# Modbus_RTU.net
KiCad netlist of a schematic drawn in Altium Designer
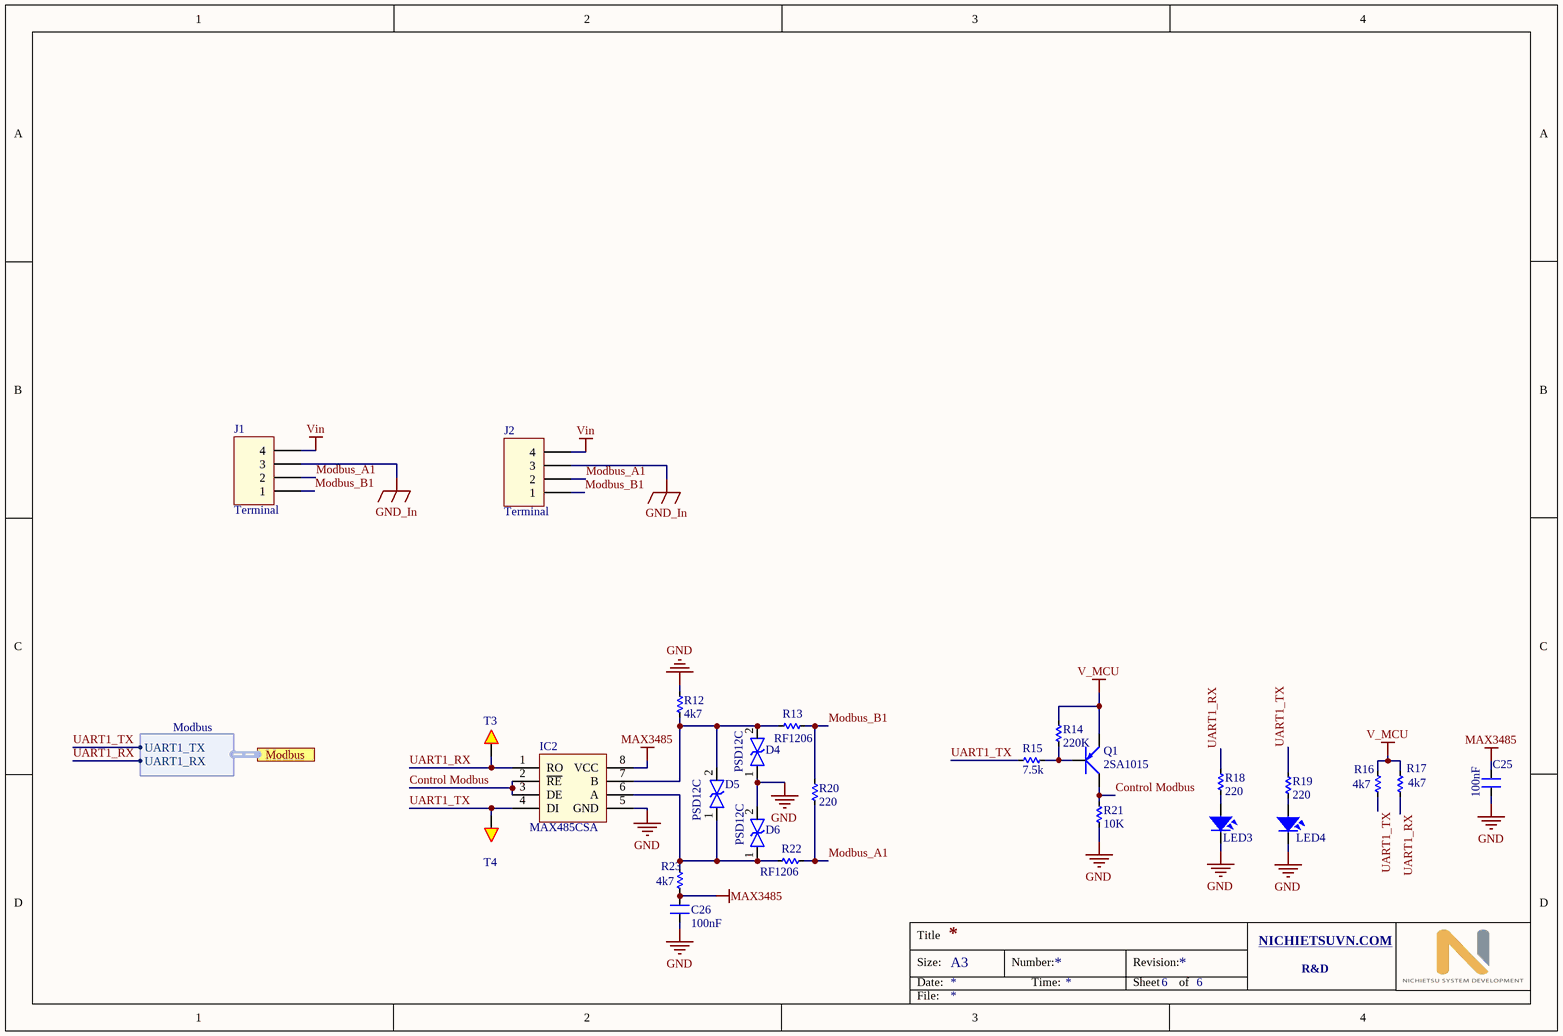
[diagram p0: Modbus RTU.SchDoc]

(export (version "E")
  (design (tool "Eeschema 10.0.6"))
  (components
    (comp (ref "C25") (value "100nF") (footprint "CN-SMD-0603") (libsource (lib "thu vien 3d") (part "CN")))
    (comp (ref "C26") (value "100nF") (footprint "CN-SMD-0603") (libsource (lib "thu vien 3d") (part "CN")))
    (comp (ref "D4")
      (value "PSD12C")
      (footprint "PSD12C")
      (description "diode tvs")
      (libsource (lib "Nichietsuvn") (part "PSD12C"))
    )
    (comp (ref "D5")
      (value "PSD12C")
      (footprint "PSD12C")
      (description "diode tvs")
      (libsource (lib "Nichietsuvn") (part "PSD12C"))
    )
    (comp (ref "D6")
      (value "PSD12C")
      (footprint "PSD12C")
      (description "diode tvs")
      (libsource (lib "Nichietsuvn") (part "PSD12C"))
    )
    (comp (ref "IC2")
      (value "MAX485CSA")
      (footprint "SO8")
      (description "RS232 - RS485 (Same sn75176)")
      (libsource (lib "thu vien 3d") (part "MAX485"))
    )
    (comp (ref "J1")
      (value "Terminal")
      (footprint "691305340004")
      (description "WR-TBL Serie 3053 - 3.81 mm Horizontal PCB Header with Plastic Latch, 04p")
      (fields (field (name "PART NUMBER") "691305340004") (field (name "PUBLISHER") "Wurth Elektronik"))
      (libsource (lib "header 3.81") (part "691305340004"))
    )
    (comp (ref "J2")
      (value "Terminal")
      (footprint "691305340004")
      (description "WR-TBL Serie 3053 - 3.81 mm Horizontal PCB Header with Plastic Latch, 04p")
      (fields (field (name "PART NUMBER") "691305340004") (field (name "PUBLISHER") "Wurth Elektronik"))
      (libsource (lib "header 3.81") (part "691305340004"))
    )
    (comp (ref "LED3")
      (value "LED")
      (footprint "LED-0805-Blue")
      (libsource (lib "thu vien 3d") (part "LED SMD"))
    )
    (comp (ref "LED4")
      (value "LED")
      (footprint "LED-0805-Blue")
      (libsource (lib "thu vien 3d") (part "LED SMD"))
    )
    (comp (ref "Q1")
      (value "2SA1015")
      (footprint "SOT23-321")
      (description "PNP 600mW, ECB")
      (libsource (lib "thu vien 3d") (part "2SA1015"))
    )
    (comp (ref "R12")
      (value "4k7")
      (footprint "RES-SMD-0603")
      (description "Resistor")
      (fields
        (field (name "MANUFACTURER") "Generic Components")
        (field (name "PUBLISHER") "Altium Hobart Technology Centre")
      )
      (libsource (lib "thu vien 3d") (part "Res-SMD"))
    )
    (comp (ref "R13")
      (value "RF1206")
      (footprint "RES-SMD-1206")
      (description "Resistor")
      (fields
        (field (name "MANUFACTURER") "Generic Components")
        (field (name "PUBLISHER") "Altium Hobart Technology Centre")
      )
      (libsource (lib "thu vien 3d") (part "Res-SMD"))
    )
    (comp (ref "R14")
      (value "220K")
      (footprint "RES-SMD-0603")
      (description "Resistor")
      (fields
        (field (name "MANUFACTURER") "Generic Components")
        (field (name "PUBLISHER") "Altium Hobart Technology Centre")
      )
      (libsource (lib "thu vien 3d") (part "Res-SMD"))
    )
    (comp (ref "R15")
      (value "7.5k")
      (footprint "RES-SMD-0603")
      (description "Resistor")
      (fields
        (field (name "MANUFACTURER") "Generic Components")
        (field (name "PUBLISHER") "Altium Hobart Technology Centre")
      )
      (libsource (lib "thu vien 3d") (part "Res-SMD"))
    )
    (comp (ref "R16")
      (value "4k7")
      (footprint "RES-SMD-0603")
      (description "Resistor")
      (fields
        (field (name "MANUFACTURER") "Generic Components")
        (field (name "PUBLISHER") "Altium Hobart Technology Centre")
      )
      (libsource (lib "thu vien 3d") (part "Res-SMD"))
    )
    (comp (ref "R17")
      (value "4k7")
      (footprint "RES-SMD-0603")
      (description "Resistor")
      (fields
        (field (name "MANUFACTURER") "Generic Components")
        (field (name "PUBLISHER") "Altium Hobart Technology Centre")
      )
      (libsource (lib "thu vien 3d") (part "Res-SMD"))
    )
    (comp (ref "R18")
      (value "220")
      (footprint "RES-SMD-0603")
      (description "Resistor")
      (fields
        (field (name "MANUFACTURER") "Generic Components")
        (field (name "PUBLISHER") "Altium Hobart Technology Centre")
      )
      (libsource (lib "thu vien 3d") (part "Res-SMD"))
    )
    (comp (ref "R19")
      (value "220")
      (footprint "RES-SMD-0603")
      (description "Resistor")
      (fields
        (field (name "MANUFACTURER") "Generic Components")
        (field (name "PUBLISHER") "Altium Hobart Technology Centre")
      )
      (libsource (lib "thu vien 3d") (part "Res-SMD"))
    )
    (comp (ref "R20")
      (value "220")
      (footprint "RES-SMD-0603")
      (description "Resistor")
      (fields
        (field (name "MANUFACTURER") "Generic Components")
        (field (name "PUBLISHER") "Altium Hobart Technology Centre")
      )
      (libsource (lib "thu vien 3d") (part "Res-SMD"))
    )
    (comp (ref "R21")
      (value "10K")
      (footprint "RES-SMD-0603")
      (description "Resistor")
      (fields
        (field (name "MANUFACTURER") "Generic Components")
        (field (name "PUBLISHER") "Altium Hobart Technology Centre")
      )
      (libsource (lib "thu vien 3d") (part "Res-SMD"))
    )
    (comp (ref "R22")
      (value "RF1206")
      (footprint "RES-SMD-1206")
      (description "Resistor")
      (fields
        (field (name "MANUFACTURER") "Generic Components")
        (field (name "PUBLISHER") "Altium Hobart Technology Centre")
      )
      (libsource (lib "thu vien 3d") (part "Res-SMD"))
    )
    (comp (ref "R23")
      (value "4k7")
      (footprint "RES-SMD-0603")
      (description "Resistor")
      (fields
        (field (name "MANUFACTURER") "Generic Components")
        (field (name "PUBLISHER") "Altium Hobart Technology Centre")
      )
      (libsource (lib "thu vien 3d") (part "Res-SMD"))
    )
    (comp (ref "T3")
      (value "Test")
      (footprint "Test")
      (description "WR-PHD 2.54 mm Angled Socket Header")
      (fields
        (field (name "MANUFACTURER") "Würth Elektronik eiSos GmbH")
        (field (name "PARTNO") "613002143121")
        (field (name "CREATED BY") "Karrer Zheng")
      )
      (libsource (lib "Nichietsuvn") (part "Test"))
    )
    (comp (ref "T4")
      (value "Test")
      (footprint "Test")
      (description "WR-PHD 2.54 mm Angled Socket Header")
      (fields
        (field (name "MANUFACTURER") "Würth Elektronik eiSos GmbH")
        (field (name "PARTNO") "613002143121")
        (field (name "CREATED BY") "Karrer Zheng")
      )
      (libsource (lib "Nichietsuvn") (part "Test"))
    )
  )
  (nets
    (net (code "2") (name "/Control Modbus") (class "Default")
      (node (ref "IC2") (pin "2") (pinfunction "~{RE}_2") (pintype "passive"))
      (node (ref "IC2") (pin "3") (pinfunction "DE_3") (pintype "passive"))
      (node (ref "Q1") (pin "2") (pinfunction "C_2") (pintype "passive"))
      (node (ref "R21") (pin "2") (pinfunction "2_2") (pintype "passive"))
    )
    (net (code "3") (name "/Modbus_A1") (class "Default")
      (node (ref "J1") (pin "2") (pinfunction "2_2") (pintype "passive"))
      (node (ref "J2") (pin "2") (pinfunction "2_2") (pintype "passive"))
      (node (ref "R20") (pin "2") (pinfunction "2_2") (pintype "passive"))
      (node (ref "R22") (pin "1") (pinfunction "1_1") (pintype "passive"))
    )
    (net (code "4") (name "/Modbus_B1") (class "Default")
      (node (ref "J1") (pin "1") (pinfunction "1_1") (pintype "passive"))
      (node (ref "J2") (pin "1") (pinfunction "1_1") (pintype "passive"))
      (node (ref "R13") (pin "1") (pinfunction "1_1") (pintype "passive"))
      (node (ref "R20") (pin "1") (pinfunction "1_1") (pintype "passive"))
    )
    (net (code "5") (name "/UART1_RX") (class "Default")
      (node (ref "IC2") (pin "1") (pinfunction "RO_1") (pintype "passive"))
      (node (ref "R17") (pin "2") (pinfunction "2_2") (pintype "passive"))
      (node (ref "R18") (pin "1") (pinfunction "1_1") (pintype "passive"))
      (node (ref "T3") (pin "1") (pinfunction "1_1") (pintype "passive"))
    )
    (net (code "6") (name "/UART1_TX") (class "Default")
      (node (ref "IC2") (pin "4") (pinfunction "DI_4") (pintype "passive"))
      (node (ref "R15") (pin "1") (pinfunction "1_1") (pintype "passive"))
      (node (ref "R16") (pin "2") (pinfunction "2_2") (pintype "passive"))
      (node (ref "R19") (pin "1") (pinfunction "1_1") (pintype "passive"))
      (node (ref "T4") (pin "1") (pinfunction "1_1") (pintype "passive"))
    )
    (net (code "8") (name "GND") (class "Default")
      (node (ref "C25") (pin "1") (pinfunction "1_1") (pintype "passive"))
      (node (ref "C26") (pin "2") (pinfunction "2_2") (pintype "passive"))
      (node (ref "D4") (pin "1") (pinfunction "1_1") (pintype "passive"))
      (node (ref "D6") (pin "2") (pinfunction "2_2") (pintype "passive"))
      (node (ref "IC2") (pin "5") (pinfunction "GND_5") (pintype "passive"))
      (node (ref "LED3") (pin "2") (pinfunction "2_2") (pintype "passive"))
      (node (ref "LED4") (pin "2") (pinfunction "2_2") (pintype "passive"))
      (node (ref "R12") (pin "1") (pinfunction "1_1") (pintype "passive"))
      (node (ref "R21") (pin "1") (pinfunction "1_1") (pintype "passive"))
    )
    (net (code "9") (name "GND_In") (class "Default")
      (node (ref "J1") (pin "3") (pinfunction "3_3") (pintype "passive"))
      (node (ref "J2") (pin "3") (pinfunction "3_3") (pintype "passive"))
    )
    (net (code "10") (name "MAX3485") (class "Default")
      (node (ref "C25") (pin "2") (pinfunction "2_2") (pintype "passive"))
      (node (ref "C26") (pin "1") (pinfunction "1_1") (pintype "passive"))
      (node (ref "IC2") (pin "8") (pinfunction "VCC_8") (pintype "passive"))
      (node (ref "R23") (pin "1") (pinfunction "1_1") (pintype "passive"))
    )
    (net (code "11") (name "Net-(IC2-A)") (class "Default")
      (node (ref "D5") (pin "1") (pinfunction "1_1") (pintype "passive"))
      (node (ref "D6") (pin "1") (pinfunction "1_1") (pintype "passive"))
      (node (ref "IC2") (pin "6") (pinfunction "A_6") (pintype "passive"))
      (node (ref "R22") (pin "2") (pinfunction "2_2") (pintype "passive"))
      (node (ref "R23") (pin "2") (pinfunction "2_2") (pintype "passive"))
    )
    (net (code "12") (name "Net-(IC2-B)") (class "Default")
      (node (ref "D4") (pin "2") (pinfunction "2_2") (pintype "passive"))
      (node (ref "D5") (pin "2") (pinfunction "2_2") (pintype "passive"))
      (node (ref "IC2") (pin "7") (pinfunction "B_7") (pintype "passive"))
      (node (ref "R12") (pin "2") (pinfunction "2_2") (pintype "passive"))
      (node (ref "R13") (pin "2") (pinfunction "2_2") (pintype "passive"))
    )
    (net (code "13") (name "Net-(LED3-Pad1)") (class "Default")
      (node (ref "LED3") (pin "1") (pinfunction "1_1") (pintype "passive"))
      (node (ref "R18") (pin "2") (pinfunction "2_2") (pintype "passive"))
    )
    (net (code "14") (name "Net-(LED4-Pad1)") (class "Default")
      (node (ref "LED4") (pin "1") (pinfunction "1_1") (pintype "passive"))
      (node (ref "R19") (pin "2") (pinfunction "2_2") (pintype "passive"))
    )
    (net (code "15") (name "Net-(Q1-B)") (class "Default")
      (node (ref "Q1") (pin "3") (pinfunction "B_3") (pintype "passive"))
      (node (ref "R14") (pin "1") (pinfunction "1_1") (pintype "passive"))
      (node (ref "R15") (pin "2") (pinfunction "2_2") (pintype "passive"))
    )
    (net (code "16") (name "V_MCU") (class "Default")
      (node (ref "Q1") (pin "1") (pinfunction "E_1") (pintype "passive"))
      (node (ref "R14") (pin "2") (pinfunction "2_2") (pintype "passive"))
      (node (ref "R16") (pin "1") (pinfunction "1_1") (pintype "passive"))
      (node (ref "R17") (pin "1") (pinfunction "1_1") (pintype "passive"))
    )
    (net (code "17") (name "Vin") (class "Default")
      (node (ref "J1") (pin "4") (pinfunction "4_4") (pintype "passive"))
      (node (ref "J2") (pin "4") (pinfunction "4_4") (pintype "passive"))
    )
  )
)
